# Schematic_Sheet.net
KiCad netlist of a schematic drawn in Altium Designer
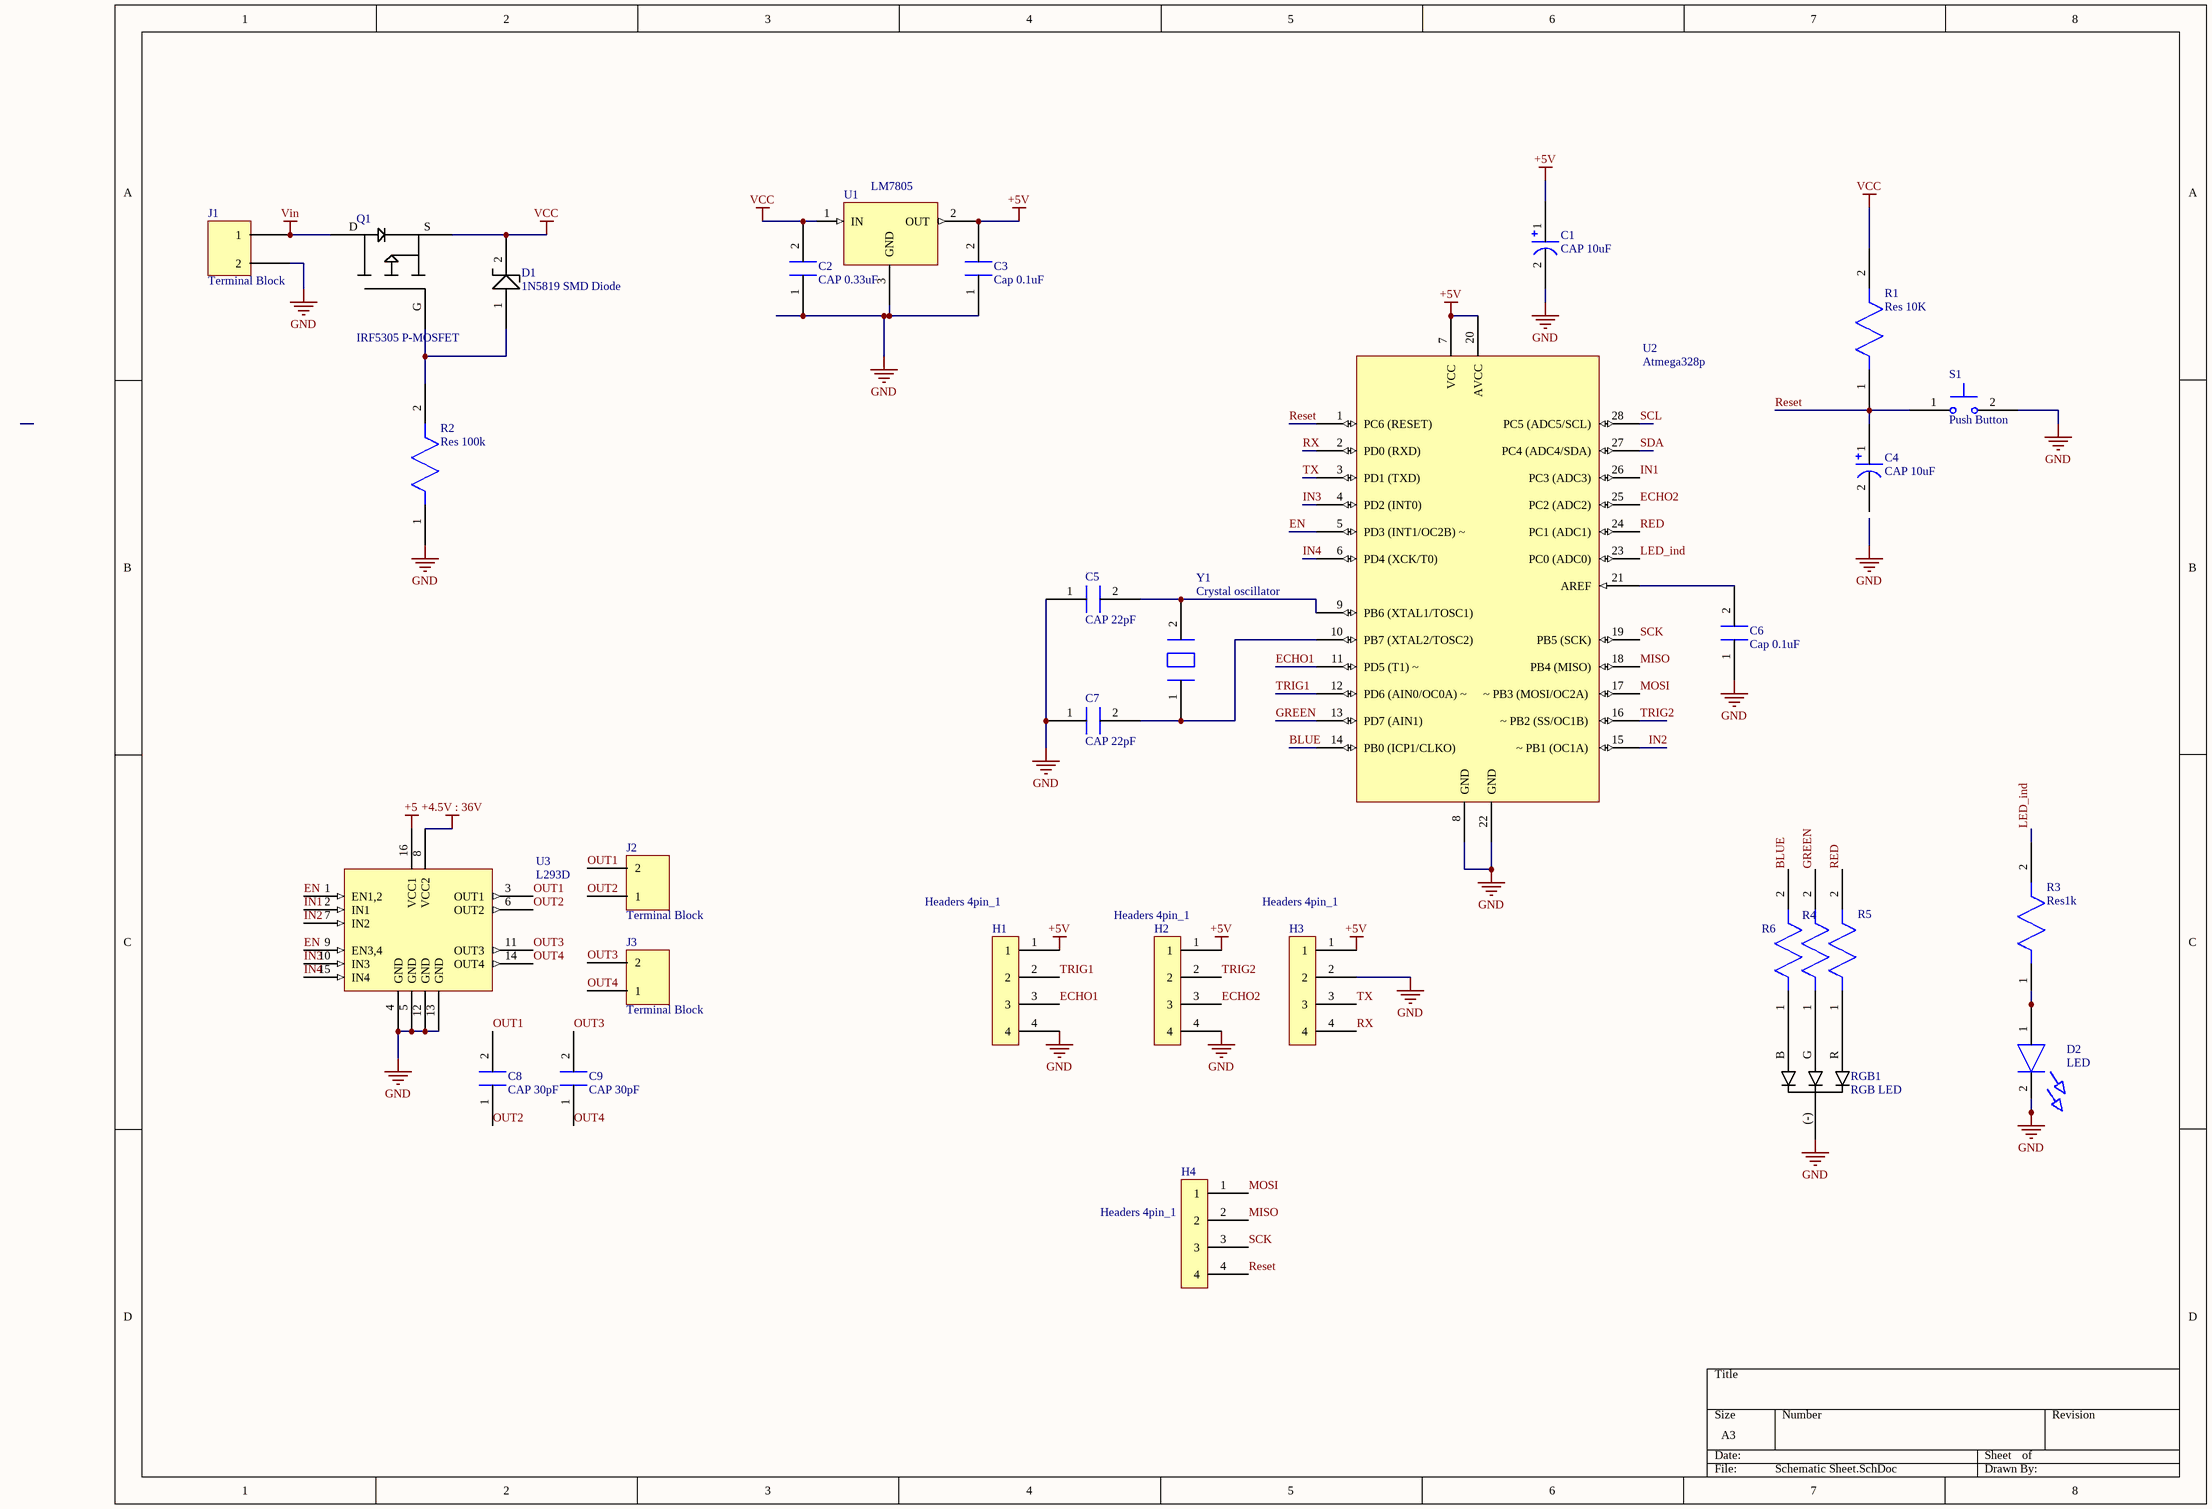
[diagram p0: Schematic Sheet.SchDoc]

(export (version "E")
  (design (tool "Eeschema 10.0.6"))
  (components
    (comp (ref "C1")
      (value "CAP 10uF")
      (footprint "Cap 10uF")
      (libsource (lib "Schematic Library") (part "CAP 10uF"))
    )
    (comp (ref "C2") (value "CAP 0.33uF") (libsource (lib "Schlib1") (part "CAP 0.33uF")))
    (comp (ref "C3") (value "Cap 0.1uF") (libsource (lib "Schlib1") (part "Cap 0.1uF")))
    (comp (ref "C4")
      (value "CAP 10uF")
      (footprint "Cap 10uF")
      (libsource (lib "Schematic Library") (part "CAP 10uF"))
    )
    (comp (ref "C5")
      (value "CAP 22pF")
      (footprint "Cap 22pF")
      (libsource (lib "Schematic Library") (part "CAP 22pF"))
    )
    (comp (ref "C6") (value "Cap 0.1uF") (libsource (lib "Schematic Library") (part "Cap 0.1uF")))
    (comp (ref "C7")
      (value "CAP 22pF")
      (footprint "Cap 22pF")
      (libsource (lib "Schematic Library") (part "CAP 22pF"))
    )
    (comp (ref "C8") (value "CAP 30pF") (libsource (lib "Schlib1") (part "CAP 30pF")))
    (comp (ref "C9") (value "CAP 30pF") (libsource (lib "Schlib1") (part "CAP 30pF")))
    (comp (ref "D1")
      (value "1N5819 SMD Diode")
      (footprint "1N5819 SMD Diode")
      (libsource (lib "Schematic Library") (part "1N5819 SMD Diode"))
    )
    (comp (ref "D2") (value "LED") (footprint "LED") (libsource (lib "Schematic Library") (part "LED")))
    (comp (ref "H1")
      (value "Headers 4pin_1")
      (footprint "Header 4pin")
      (libsource (lib "Schematic Library") (part "Headers 4pin_1"))
    )
    (comp (ref "H2")
      (value "Headers 4pin_1")
      (footprint "Header 4pin")
      (libsource (lib "Schematic Library") (part "Headers 4pin_1"))
    )
    (comp (ref "H3")
      (value "Headers 4pin_1")
      (footprint "Header 4pin")
      (libsource (lib "Schematic Library") (part "Headers 4pin_1"))
    )
    (comp (ref "H4")
      (value "Headers 4pin_1")
      (footprint "Header 4pin")
      (libsource (lib "Schematic Library") (part "Headers 4pin_1"))
    )
    (comp (ref "J1")
      (value "Terminal Block")
      (footprint "Terminal Block 2pin")
      (libsource (lib "Schematic Library") (part "Terminal Block"))
    )
    (comp (ref "J2")
      (value "Terminal Block")
      (footprint "Terminal Block 2pin")
      (libsource (lib "") (part "Terminal Block_1"))
    )
    (comp (ref "J3")
      (value "Terminal Block")
      (footprint "Terminal Block 2pin")
      (libsource (lib "") (part "Terminal Block_1"))
    )
    (comp (ref "Q1")
      (value "IRF5305 P-MOSFET")
      (footprint "IRF5305")
      (libsource (lib "Schematic Library") (part "IRF5305 P-MOSFET"))
    )
    (comp (ref "R1")
      (value "Res 10K")
      (footprint "Res10K")
      (libsource (lib "Schematic Library") (part "Res 10K"))
    )
    (comp (ref "R2")
      (value "Res 100k")
      (footprint "Res100K")
      (libsource (lib "Schematic Library") (part "Res 100k"))
    )
    (comp (ref "R3")
      (value "Res1k")
      (footprint "Res 1K")
      (libsource (lib "Schematic Library") (part "Res1k"))
    )
    (comp (ref "R4") (value "Resistor") (libsource (lib "Schematic Library") (part "Resistor")))
    (comp (ref "R5") (value "Resistor") (libsource (lib "Schematic Library") (part "Resistor")))
    (comp (ref "R6") (value "Resistor") (libsource (lib "Schematic Library") (part "Resistor")))
    (comp (ref "RGB1")
      (value "RGB LED")
      (footprint "RGB LED")
      (libsource (lib "Schematic Library") (part "RGB LED"))
    )
    (comp (ref "S1")
      (value "Push Button")
      (footprint "Push Button")
      (libsource (lib "Schematic Library") (part "Push Button"))
    )
    (comp (ref "U1")
      (value "LM7805")
      (footprint "LM7805")
      (libsource (lib "Schematic Library") (part "LM7805"))
    )
    (comp (ref "U2")
      (value "Atmega328p")
      (footprint "ATMega 328 P-PU - duplicate")
      (libsource (lib "Schematic Library") (part "Atmega328p"))
    )
    (comp (ref "U3") (value "L293D") (footprint "L293D") (libsource (lib "Schematic Library") (part "L293D")))
    (comp (ref "Y1")
      (value "Crystal oscillator")
      (footprint "Crrystal 16MHZ")
      (libsource (lib "Schematic Library") (part "Crystal oscillator"))
    )
  )
  (nets
    (net (code "1") (name "+4.5V : 36V") (class "Default")
      (node (ref "U3") (pin "8") (pinfunction "VCC2_8") (pintype "power_in"))
    )
    (net (code "2") (name "+5") (class "Default")
      (node (ref "U3") (pin "16") (pinfunction "VCC1_16") (pintype "power_in"))
    )
    (net (code "3") (name "+5V") (class "Default")
      (node (ref "C1") (pin "1") (pinfunction "1_1") (pintype "passive"))
      (node (ref "C3") (pin "2") (pinfunction "2_2") (pintype "passive"))
      (node (ref "H1") (pin "1") (pinfunction "1_1") (pintype "passive"))
      (node (ref "H2") (pin "1") (pinfunction "1_1") (pintype "passive"))
      (node (ref "H3") (pin "1") (pinfunction "1_1") (pintype "passive"))
      (node (ref "U1") (pin "2") (pinfunction "OUT_2") (pintype "output"))
      (node (ref "U2") (pin "20") (pinfunction "AVCC_20") (pintype "passive"))
      (node (ref "U2") (pin "7") (pinfunction "VCC_7") (pintype "passive"))
    )
    (net (code "5") (name "/BLUE") (class "Default")
      (node (ref "R6") (pin "2") (pinfunction "4_2") (pintype "passive"))
      (node (ref "U2") (pin "14") (pinfunction "PB0_(ICP1/CLKO)_14") (pintype "bidirectional"))
    )
    (net (code "6") (name "/ECHO1") (class "Default")
      (node (ref "H1") (pin "3") (pinfunction "3_3") (pintype "passive"))
      (node (ref "U2") (pin "11") (pinfunction "PD5_(T1)_~_11") (pintype "bidirectional"))
    )
    (net (code "7") (name "/ECHO2") (class "Default")
      (node (ref "H2") (pin "3") (pinfunction "3_3") (pintype "passive"))
      (node (ref "U2") (pin "25") (pinfunction "PC2_(ADC2)_25") (pintype "bidirectional"))
    )
    (net (code "8") (name "/EN") (class "Default")
      (node (ref "U2") (pin "5") (pinfunction "PD3_(INT1/OC2B)_~_5") (pintype "bidirectional"))
      (node (ref "U3") (pin "1") (pinfunction "EN1,2_1") (pintype "input"))
      (node (ref "U3") (pin "9") (pinfunction "EN3,4_9") (pintype "input"))
    )
    (net (code "9") (name "/GREEN") (class "Default")
      (node (ref "R4") (pin "2") (pinfunction "4_2") (pintype "passive"))
      (node (ref "U2") (pin "13") (pinfunction "PD7_(AIN1)_13") (pintype "bidirectional"))
    )
    (net (code "10") (name "/IN1") (class "Default")
      (node (ref "U2") (pin "26") (pinfunction "PC3_(ADC3)_26") (pintype "bidirectional"))
      (node (ref "U3") (pin "2") (pinfunction "IN1_2") (pintype "input"))
    )
    (net (code "11") (name "/IN2") (class "Default")
      (node (ref "U2") (pin "15") (pinfunction "~_PB1_(OC1A)_15") (pintype "bidirectional"))
      (node (ref "U3") (pin "7") (pinfunction "IN2_7") (pintype "input"))
    )
    (net (code "12") (name "/IN3") (class "Default")
      (node (ref "U2") (pin "4") (pinfunction "PD2_(INT0)_4") (pintype "bidirectional"))
      (node (ref "U3") (pin "10") (pinfunction "IN3_10") (pintype "input"))
    )
    (net (code "13") (name "/IN4") (class "Default")
      (node (ref "U2") (pin "6") (pinfunction "PD4_(XCK/T0)_6") (pintype "bidirectional"))
      (node (ref "U3") (pin "15") (pinfunction "IN4_15") (pintype "input"))
    )
    (net (code "14") (name "/LED_ind") (class "Default")
      (node (ref "R3") (pin "2") (pinfunction "4_2") (pintype "passive"))
      (node (ref "U2") (pin "23") (pinfunction "PC0_(ADC0)_23") (pintype "bidirectional"))
    )
    (net (code "15") (name "/MISO") (class "Default")
      (node (ref "H4") (pin "2") (pinfunction "2_2") (pintype "passive"))
      (node (ref "U2") (pin "18") (pinfunction "PB4_(MISO)_18") (pintype "bidirectional"))
    )
    (net (code "16") (name "/MOSI") (class "Default")
      (node (ref "H4") (pin "1") (pinfunction "1_1") (pintype "passive"))
      (node (ref "U2") (pin "17") (pinfunction "~_PB3_(MOSI/OC2A)_17") (pintype "bidirectional"))
    )
    (net (code "17") (name "/OUT1") (class "Default")
      (node (ref "C8") (pin "2") (pinfunction "2_2") (pintype "passive"))
      (node (ref "J2") (pin "2") (pinfunction "2_2") (pintype "passive"))
      (node (ref "U3") (pin "3") (pinfunction "OUT1_3") (pintype "output"))
    )
    (net (code "18") (name "/OUT2") (class "Default")
      (node (ref "C8") (pin "1") (pinfunction "1_1") (pintype "passive"))
      (node (ref "J2") (pin "1") (pinfunction "1_1") (pintype "passive"))
      (node (ref "U3") (pin "6") (pinfunction "OUT2_6") (pintype "output"))
    )
    (net (code "19") (name "/OUT3") (class "Default")
      (node (ref "C9") (pin "2") (pinfunction "2_2") (pintype "passive"))
      (node (ref "J3") (pin "2") (pinfunction "2_2") (pintype "passive"))
      (node (ref "U3") (pin "11") (pinfunction "OUT3_11") (pintype "output"))
    )
    (net (code "20") (name "/OUT4") (class "Default")
      (node (ref "C9") (pin "1") (pinfunction "1_1") (pintype "passive"))
      (node (ref "J3") (pin "1") (pinfunction "1_1") (pintype "passive"))
      (node (ref "U3") (pin "14") (pinfunction "OUT4_14") (pintype "output"))
    )
    (net (code "21") (name "/RED") (class "Default")
      (node (ref "R5") (pin "2") (pinfunction "4_2") (pintype "passive"))
      (node (ref "U2") (pin "24") (pinfunction "PC1_(ADC1)_24") (pintype "bidirectional"))
    )
    (net (code "22") (name "/RX") (class "Default")
      (node (ref "H3") (pin "4") (pinfunction "4_4") (pintype "passive"))
      (node (ref "U2") (pin "2") (pinfunction "PD0_(RXD)_2") (pintype "bidirectional"))
    )
    (net (code "23") (name "/Reset") (class "Default")
      (node (ref "C4") (pin "1") (pinfunction "1_1") (pintype "passive"))
      (node (ref "H4") (pin "4") (pinfunction "4_4") (pintype "passive"))
      (node (ref "R1") (pin "1") (pinfunction "3_1") (pintype "passive"))
      (node (ref "S1") (pin "1") (pinfunction "76_1") (pintype "passive"))
      (node (ref "U2") (pin "1") (pinfunction "PC6_(RESET)_1") (pintype "bidirectional"))
    )
    (net (code "24") (name "/SCK") (class "Default")
      (node (ref "H4") (pin "3") (pinfunction "3_3") (pintype "passive"))
      (node (ref "U2") (pin "19") (pinfunction "PB5_(SCK)_19") (pintype "bidirectional"))
    )
    (net (code "25") (name "/SCL") (class "Default")
      (node (ref "U2") (pin "28") (pinfunction "PC5_(ADC5/SCL)_28") (pintype "bidirectional"))
    )
    (net (code "26") (name "/SDA") (class "Default")
      (node (ref "U2") (pin "27") (pinfunction "PC4_(ADC4/SDA)_27") (pintype "bidirectional"))
    )
    (net (code "27") (name "/TRIG1") (class "Default")
      (node (ref "H1") (pin "2") (pinfunction "2_2") (pintype "passive"))
      (node (ref "U2") (pin "12") (pinfunction "PD6_(AIN0/OC0A)_~_12") (pintype "bidirectional"))
    )
    (net (code "28") (name "/TRIG2") (class "Default")
      (node (ref "H2") (pin "2") (pinfunction "2_2") (pintype "passive"))
      (node (ref "U2") (pin "16") (pinfunction "~_PB2_(SS/OC1B)_16") (pintype "bidirectional"))
    )
    (net (code "29") (name "/TX") (class "Default")
      (node (ref "H3") (pin "3") (pinfunction "3_3") (pintype "passive"))
      (node (ref "U2") (pin "3") (pinfunction "PD1_(TXD)_3") (pintype "bidirectional"))
    )
    (net (code "30") (name "GND") (class "Default")
      (node (ref "C1") (pin "2") (pinfunction "2_2") (pintype "passive"))
      (node (ref "C2") (pin "1") (pinfunction "1_1") (pintype "passive"))
      (node (ref "C3") (pin "1") (pinfunction "1_1") (pintype "passive"))
      (node (ref "C5") (pin "1") (pinfunction "1_1") (pintype "passive"))
      (node (ref "C6") (pin "1") (pinfunction "1_1") (pintype "passive"))
      (node (ref "C7") (pin "1") (pinfunction "1_1") (pintype "passive"))
      (node (ref "D2") (pin "2") (pinfunction "6_2") (pintype "passive"))
      (node (ref "H1") (pin "4") (pinfunction "4_4") (pintype "passive"))
      (node (ref "H2") (pin "4") (pinfunction "4_4") (pintype "passive"))
      (node (ref "H3") (pin "2") (pinfunction "2_2") (pintype "passive"))
      (node (ref "J1") (pin "2") (pinfunction "2_2") (pintype "passive"))
      (node (ref "R2") (pin "1") (pinfunction "3_1") (pintype "passive"))
      (node (ref "RGB1") (pin "(-)") (pinfunction "1_(-)") (pintype "passive"))
      (node (ref "S1") (pin "2") (pinfunction "77_2") (pintype "passive"))
      (node (ref "U1") (pin "3") (pinfunction "GND_3") (pintype "power_in"))
      (node (ref "U2") (pin "22") (pinfunction "GND_22") (pintype "passive"))
      (node (ref "U2") (pin "8") (pinfunction "GND_8") (pintype "passive"))
      (node (ref "U3") (pin "12") (pinfunction "GND_12") (pintype "power_in"))
      (node (ref "U3") (pin "13") (pinfunction "GND_13") (pintype "power_in"))
      (node (ref "U3") (pin "4") (pinfunction "GND_4") (pintype "power_in"))
      (node (ref "U3") (pin "5") (pinfunction "GND_5") (pintype "power_in"))
    )
    (net (code "31") (name "Net-(D2-7)") (class "Default")
      (node (ref "D2") (pin "1") (pinfunction "7_1") (pintype "passive"))
      (node (ref "R3") (pin "1") (pinfunction "3_1") (pintype "passive"))
    )
    (net (code "32") (name "Net-(Q1-1)") (class "Default")
      (node (ref "D1") (pin "1") (pinfunction "1_1") (pintype "passive"))
      (node (ref "Q1") (pin "G") (pinfunction "1_G") (pintype "passive"))
      (node (ref "R2") (pin "2") (pinfunction "4_2") (pintype "passive"))
    )
    (net (code "33") (name "Net-(R4-3)") (class "Default")
      (node (ref "R4") (pin "1") (pinfunction "3_1") (pintype "passive"))
      (node (ref "RGB1") (pin "G") (pinfunction "3_G") (pintype "passive"))
    )
    (net (code "34") (name "Net-(R5-3)") (class "Default")
      (node (ref "R5") (pin "1") (pinfunction "3_1") (pintype "passive"))
      (node (ref "RGB1") (pin "R") (pinfunction "2_R") (pintype "passive"))
    )
    (net (code "35") (name "Net-(R6-3)") (class "Default")
      (node (ref "R6") (pin "1") (pinfunction "3_1") (pintype "passive"))
      (node (ref "RGB1") (pin "B") (pinfunction "4_B") (pintype "passive"))
    )
    (net (code "36") (name "Net-(U2-AREF)") (class "Default")
      (node (ref "C6") (pin "2") (pinfunction "2_2") (pintype "passive"))
      (node (ref "U2") (pin "21") (pinfunction "AREF_21") (pintype "input"))
    )
    (net (code "37") (name "Net-(U2-PB6_(XTAL1{slash}TOSC1))") (class "Default")
      (node (ref "C5") (pin "2") (pinfunction "2_2") (pintype "passive"))
      (node (ref "U2") (pin "9") (pinfunction "PB6_(XTAL1/TOSC1)_9") (pintype "bidirectional"))
      (node (ref "Y1") (pin "2") (pinfunction "2_2") (pintype "passive"))
    )
    (net (code "38") (name "Net-(U2-PB7_(XTAL2{slash}TOSC2))") (class "Default")
      (node (ref "C7") (pin "2") (pinfunction "2_2") (pintype "passive"))
      (node (ref "U2") (pin "10") (pinfunction "PB7_(XTAL2/TOSC2)_10") (pintype "bidirectional"))
      (node (ref "Y1") (pin "1") (pinfunction "1_1") (pintype "passive"))
    )
    (net (code "39") (name "VCC") (class "Default")
      (node (ref "C2") (pin "2") (pinfunction "2_2") (pintype "passive"))
      (node (ref "D1") (pin "2") (pinfunction "2_2") (pintype "passive"))
      (node (ref "Q1") (pin "S") (pinfunction "2_S") (pintype "passive"))
      (node (ref "R1") (pin "2") (pinfunction "4_2") (pintype "passive"))
      (node (ref "U1") (pin "1") (pinfunction "IN_1") (pintype "input"))
    )
    (net (code "40") (name "Vin") (class "Default")
      (node (ref "J1") (pin "1") (pinfunction "1_1") (pintype "passive"))
      (node (ref "Q1") (pin "D") (pinfunction "3_D") (pintype "passive"))
    )
    (net (code "41") (name "unconnected-(C4-Pad2)") (class "Default")
      (node (ref "C4") (pin "2") (pinfunction "2_2") (pintype "passive"))
    )
  )
)
